# 28pws.net
KiCad netlist of a schematic drawn in EAGLE
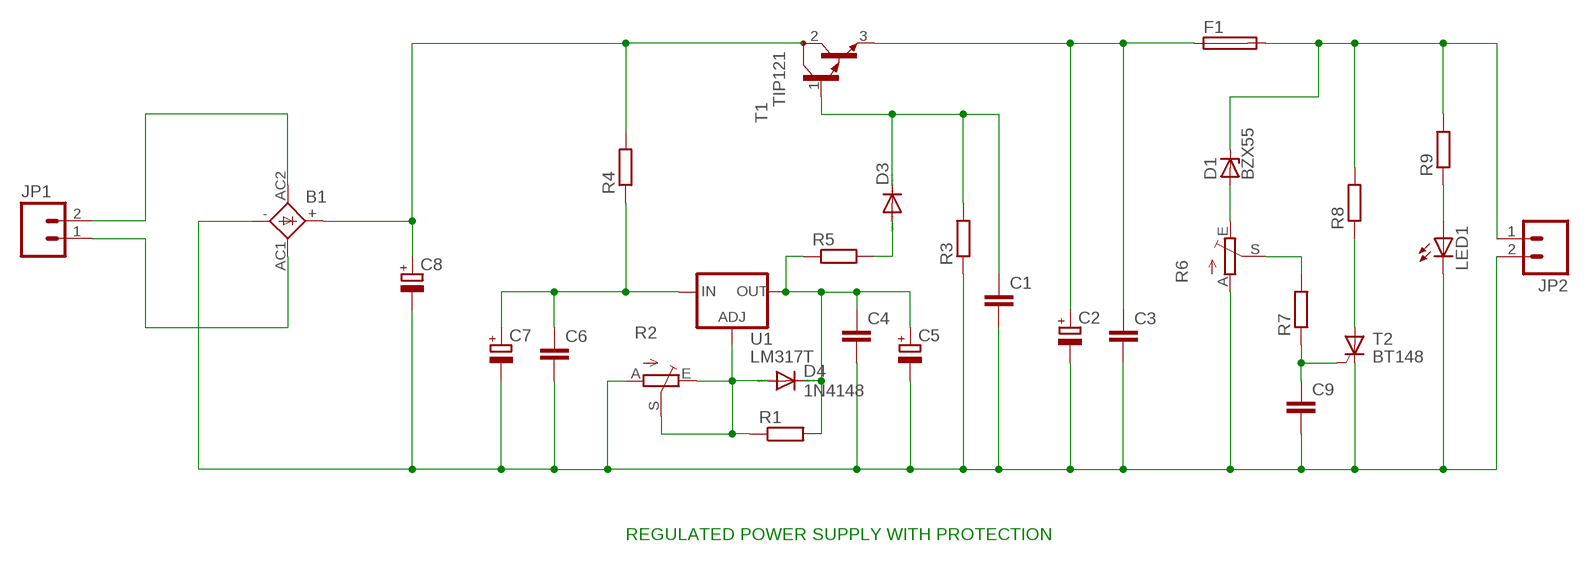
[diagram p0: schematic, sheet 1]

(export (version "E")
  (design (tool "Eeschema 10.0.6"))
  (components
    (comp (ref "B1")
      (value "GBU4S")
      (footprint "eagle-import:GBU4S")
      (libsource (lib "eagle-import") (part "GBU4S"))
    )
    (comp (ref "C1")
      (value "C-EU025-025X050")
      (footprint "eagle-import:C025-025X050")
      (libsource (lib "eagle-import") (part "C-EU025-025X050"))
    )
    (comp (ref "C2")
      (value "CPOL-EUE5-13")
      (footprint "eagle-import:E5-13")
      (libsource (lib "eagle-import") (part "resistor_CPOL-EUE5-13"))
    )
    (comp (ref "C3")
      (value "C-EU025-025X050")
      (footprint "eagle-import:C025-025X050")
      (libsource (lib "eagle-import") (part "C-EU025-025X050"))
    )
    (comp (ref "C4")
      (value "C-EU025-025X050")
      (footprint "eagle-import:C025-025X050")
      (libsource (lib "eagle-import") (part "C-EU025-025X050"))
    )
    (comp (ref "C5")
      (value "CPOL-EUE2.5-5")
      (footprint "eagle-import:E2,5-5")
      (libsource (lib "eagle-import") (part "resistor_CPOL-EUE2.5-5"))
    )
    (comp (ref "C6")
      (value "C-EU025-025X050")
      (footprint "eagle-import:C025-025X050")
      (libsource (lib "eagle-import") (part "C-EU025-025X050"))
    )
    (comp (ref "C7")
      (value "CPOL-EUE2.5-5")
      (footprint "eagle-import:E2,5-5")
      (libsource (lib "eagle-import") (part "resistor_CPOL-EUE2.5-5"))
    )
    (comp (ref "C8")
      (value "CPOL-EUE7.5-16")
      (footprint "eagle-import:E7,5-16")
      (libsource (lib "eagle-import") (part "CPOL-EUE7.5-16"))
    )
    (comp (ref "C9")
      (value "C-EU025-025X050")
      (footprint "eagle-import:C025-025X050")
      (libsource (lib "eagle-import") (part "C-EU025-025X050"))
    )
    (comp (ref "D1")
      (value "BZX55")
      (footprint "eagle-import:DO35Z10")
      (libsource (lib "eagle-import") (part "BZX55"))
    )
    (comp (ref "D3")
      (value "DIODE-DO41-7.6")
      (footprint "eagle-import:DO41-7.6")
      (libsource (lib "eagle-import") (part "DIODE-DO41-7.6"))
    )
    (comp (ref "D4")
      (value "1N4148")
      (footprint "eagle-import:DO35-7")
      (libsource (lib "eagle-import") (part "1N4148DO35-7"))
    )
    (comp (ref "F1")
      (value "19560")
      (footprint "eagle-import:19560")
      (fields (field (name "MPN") "56000001009"))
      (libsource (lib "eagle-import") (part "19560"))
    )
    (comp (ref "JP1")
      (value "M02POGO_PIN_HOLES_ONLY")
      (footprint "eagle-import:1X02_PP_HOLES_ONLY")
      (libsource (lib "eagle-import") (part "M02POGO_PIN_HOLES_ONLY"))
    )
    (comp (ref "JP2")
      (value "M02POGO_PIN_HOLES_ONLY")
      (footprint "eagle-import:1X02_PP_HOLES_ONLY")
      (libsource (lib "eagle-import") (part "M02POGO_PIN_HOLES_ONLY"))
    )
    (comp (ref "LED1")
      (value "LED5MM")
      (footprint "eagle-import:LED5MM")
      (libsource (lib "eagle-import") (part "LED5MM"))
    )
    (comp (ref "R1")
      (value "R-EU_0204/7")
      (footprint "eagle-import:0204_7")
      (libsource (lib "eagle-import") (part "resistor_R-EU_0204/7"))
    )
    (comp (ref "R2")
      (value "TRIM_EU-RJ9W")
      (footprint "eagle-import:RJ9W")
      (libsource (lib "eagle-import") (part "TRIM_EU-RJ9W"))
    )
    (comp (ref "R3")
      (value "R-EU_0204/2V")
      (footprint "eagle-import:0204V")
      (libsource (lib "eagle-import") (part "R-EU_0204/2V"))
    )
    (comp (ref "R4")
      (value "R-EU_0411/3V")
      (footprint "eagle-import:0411V")
      (libsource (lib "eagle-import") (part "resistor_R-EU_0411/3V"))
    )
    (comp (ref "R5")
      (value "R-EU_0204/2V")
      (footprint "eagle-import:0204V")
      (libsource (lib "eagle-import") (part "R-EU_0204/2V"))
    )
    (comp (ref "R6")
      (value "TRIM_EU-B25P")
      (footprint "eagle-import:B25P")
      (libsource (lib "eagle-import") (part "TRIM_EU-B25P"))
    )
    (comp (ref "R7")
      (value "R-EU_0207/10")
      (footprint "eagle-import:0207_10")
      (libsource (lib "eagle-import") (part "R-EU_0207/10"))
    )
    (comp (ref "R8")
      (value "R-EU_VTA54")
      (footprint "eagle-import:VTA54")
      (libsource (lib "eagle-import") (part "R-EU_VTA54"))
    )
    (comp (ref "R9")
      (value "R-EU_0204/7")
      (footprint "eagle-import:0204_7")
      (libsource (lib "eagle-import") (part "resistor_R-EU_0204/7"))
    )
    (comp (ref "T1")
      (value "TIP121")
      (footprint "eagle-import:TO220")
      (libsource (lib "eagle-import") (part "TIP122"))
    )
    (comp (ref "T2")
      (value "BT148")
      (footprint "eagle-import:SOT82S")
      (libsource (lib "eagle-import") (part "BT148"))
    )
    (comp (ref "U1")
      (value "LM317T")
      (footprint "eagle-import:TO220-ADJ")
      (libsource (lib "eagle-import") (part "V_REG_317SINK"))
    )
  )
  (nets
    (net (code "1") (name "Net-(B1-AC1)") (class "Default")
      (node (ref "B1") (pin "AC2") (pinfunction "AC1_AC2") (pintype "passive"))
      (node (ref "JP1") (pin "2") (pinfunction "2_2") (pintype "passive"))
    )
    (net (code "2") (name "Net-(B1-AC2)") (class "Default")
      (node (ref "B1") (pin "AC1") (pinfunction "AC2_AC1") (pintype "passive"))
      (node (ref "JP1") (pin "1") (pinfunction "1_1") (pintype "passive"))
    )
    (net (code "3") (name "Net-(C4-Pad1)") (class "Default")
      (node (ref "C4") (pin "1") (pinfunction "1_1") (pintype "passive"))
      (node (ref "C5") (pin "+") (pinfunction "+_+") (pintype "passive"))
      (node (ref "D4") (pin "C") (pinfunction "C_C") (pintype "passive"))
      (node (ref "R1") (pin "2") (pinfunction "2_2") (pintype "passive"))
      (node (ref "R5") (pin "1") (pinfunction "1_1") (pintype "passive"))
      (node (ref "U1") (pin "OUT") (pinfunction "OUT_OUT") (pintype "output"))
    )
    (net (code "4") (name "Net-(C6-Pad1)") (class "Default")
      (node (ref "C6") (pin "1") (pinfunction "1_1") (pintype "passive"))
      (node (ref "C7") (pin "+") (pinfunction "+_+") (pintype "passive"))
      (node (ref "R4") (pin "1") (pinfunction "1_1") (pintype "passive"))
      (node (ref "U1") (pin "IN") (pinfunction "IN_IN") (pintype "input"))
    )
    (net (code "5") (name "Net-(C9-Pad1)") (class "Default")
      (node (ref "C9") (pin "1") (pinfunction "1_1") (pintype "passive"))
      (node (ref "R7") (pin "1") (pinfunction "1_1") (pintype "passive"))
      (node (ref "T2") (pin "G") (pinfunction "G_G") (pintype "passive"))
    )
    (net (code "6") (name "Net-(D1-PadA)") (class "Default")
      (node (ref "D1") (pin "A") (pinfunction "A_A") (pintype "passive"))
      (node (ref "R6") (pin "E") (pinfunction "E_E") (pintype "passive"))
    )
    (net (code "7") (name "Net-(D1-PadC)") (class "Default")
      (node (ref "D1") (pin "C") (pinfunction "C_C") (pintype "passive"))
      (node (ref "F1") (pin "2") (pinfunction "2_2") (pintype "passive"))
      (node (ref "JP2") (pin "1") (pinfunction "1_1") (pintype "passive"))
      (node (ref "R8") (pin "2") (pinfunction "2_2") (pintype "passive"))
      (node (ref "R9") (pin "2") (pinfunction "2_2") (pintype "passive"))
    )
    (net (code "8") (name "Net-(D3-PadA)") (class "Default")
      (node (ref "D3") (pin "A") (pinfunction "A_A") (pintype "passive"))
      (node (ref "R5") (pin "2") (pinfunction "2_2") (pintype "passive"))
    )
    (net (code "9") (name "Net-(D4-PadA)") (class "Default")
      (node (ref "D4") (pin "A") (pinfunction "A_A") (pintype "passive"))
      (node (ref "R1") (pin "1") (pinfunction "1_1") (pintype "passive"))
      (node (ref "R2") (pin "E") (pinfunction "E_E") (pintype "passive"))
      (node (ref "R2") (pin "S") (pinfunction "S_S") (pintype "passive"))
      (node (ref "U1") (pin "ADJ") (pinfunction "ADJ_ADJ") (pintype "input"))
    )
    (net (code "10") (name "Net-(LED1-C)") (class "Default")
      (node (ref "B1") (pin "-") (pinfunction "-_-") (pintype "passive"))
      (node (ref "C1") (pin "2") (pinfunction "2_2") (pintype "passive"))
      (node (ref "C2") (pin "-") (pinfunction "-_-") (pintype "passive"))
      (node (ref "C3") (pin "2") (pinfunction "2_2") (pintype "passive"))
      (node (ref "C4") (pin "2") (pinfunction "2_2") (pintype "passive"))
      (node (ref "C5") (pin "-") (pinfunction "-_-") (pintype "passive"))
      (node (ref "C6") (pin "2") (pinfunction "2_2") (pintype "passive"))
      (node (ref "C7") (pin "-") (pinfunction "-_-") (pintype "passive"))
      (node (ref "C8") (pin "-") (pinfunction "-_-") (pintype "passive"))
      (node (ref "C9") (pin "2") (pinfunction "2_2") (pintype "passive"))
      (node (ref "JP2") (pin "2") (pinfunction "2_2") (pintype "passive"))
      (node (ref "LED1") (pin "K") (pinfunction "C_K") (pintype "passive"))
      (node (ref "R2") (pin "A") (pinfunction "A_A") (pintype "passive"))
      (node (ref "R3") (pin "1") (pinfunction "1_1") (pintype "passive"))
      (node (ref "R6") (pin "A") (pinfunction "A_A") (pintype "passive"))
      (node (ref "T2") (pin "C") (pinfunction "C_C") (pintype "passive"))
    )
    (net (code "11") (name "Net-(LED1-PadA)") (class "Default")
      (node (ref "LED1") (pin "A") (pinfunction "A_A") (pintype "passive"))
      (node (ref "R9") (pin "1") (pinfunction "1_1") (pintype "passive"))
    )
    (net (code "12") (name "Net-(R6-PadS)") (class "Default")
      (node (ref "R6") (pin "S") (pinfunction "S_S") (pintype "passive"))
      (node (ref "R7") (pin "2") (pinfunction "2_2") (pintype "passive"))
    )
    (net (code "13") (name "Net-(R8-Pad1)") (class "Default")
      (node (ref "R8") (pin "1") (pinfunction "1_1") (pintype "passive"))
      (node (ref "T2") (pin "A") (pinfunction "A_A") (pintype "passive"))
    )
    (net (code "14") (name "Net-(T1-B)") (class "Default")
      (node (ref "C1") (pin "1") (pinfunction "1_1") (pintype "passive"))
      (node (ref "D3") (pin "C") (pinfunction "C_C") (pintype "passive"))
      (node (ref "R3") (pin "2") (pinfunction "2_2") (pintype "passive"))
      (node (ref "T1") (pin "1") (pinfunction "B_1") (pintype "passive"))
    )
    (net (code "15") (name "Net-(T1-C)") (class "Default")
      (node (ref "B1") (pin "+") (pinfunction "+_+") (pintype "passive"))
      (node (ref "C8") (pin "+") (pinfunction "+_+") (pintype "passive"))
      (node (ref "R4") (pin "2") (pinfunction "2_2") (pintype "passive"))
      (node (ref "T1") (pin "2") (pinfunction "C_2") (pintype "passive"))
    )
    (net (code "16") (name "Net-(T1-E)") (class "Default")
      (node (ref "C2") (pin "+") (pinfunction "+_+") (pintype "passive"))
      (node (ref "C3") (pin "1") (pinfunction "1_1") (pintype "passive"))
      (node (ref "F1") (pin "1") (pinfunction "1_1") (pintype "passive"))
      (node (ref "T1") (pin "3") (pinfunction "E_3") (pintype "passive"))
    )
  )
)
